# ProyectoArduino.net
KiCad netlist of a schematic drawn in EAGLE
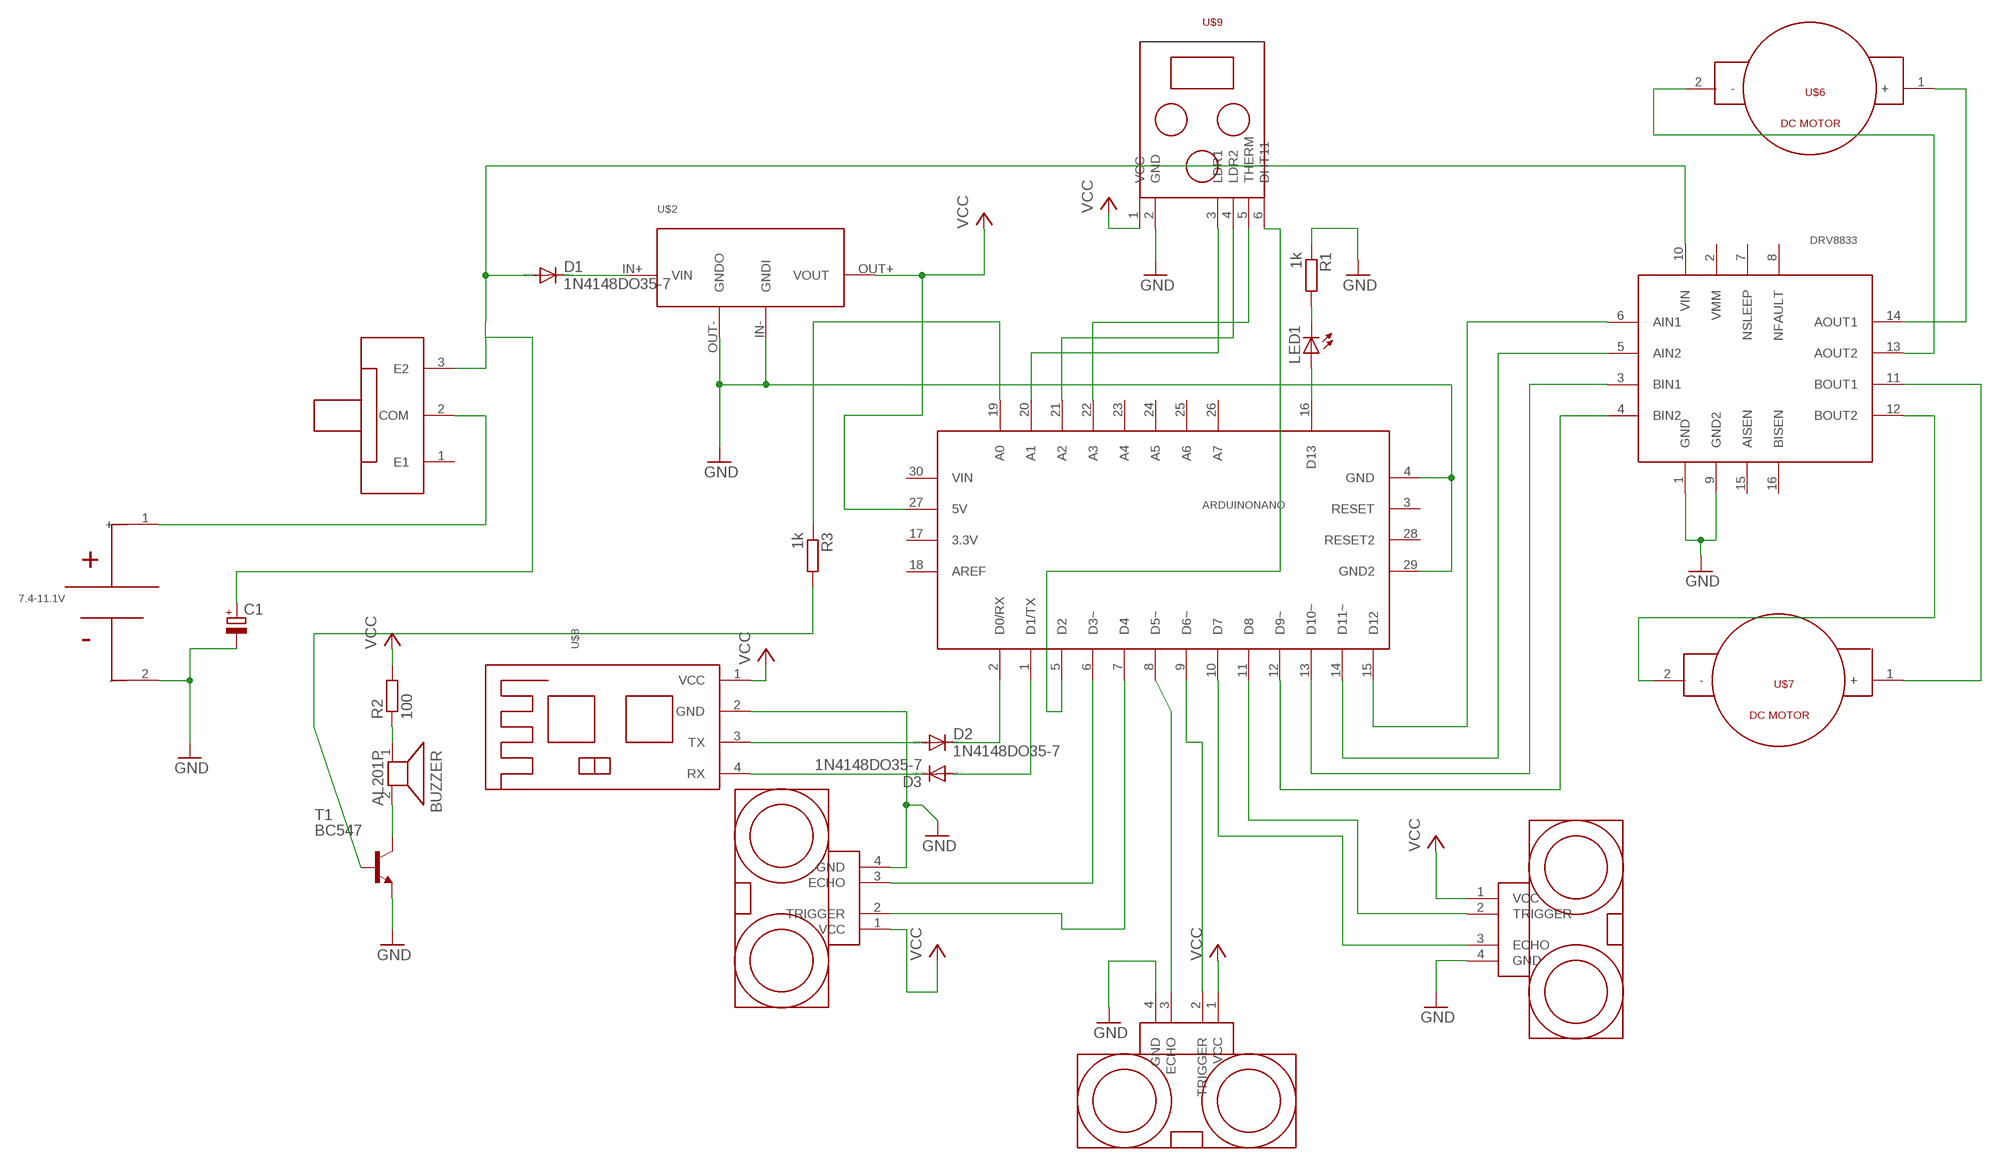
[diagram p0: schematic, sheet 1]

(export (version "E")
  (design (tool "Eeschema 10.0.6"))
  (components
    (comp (ref "7.4-11.1V")
      (value "INBAT")
      (footprint "eagle-import:INBAT")
      (libsource (lib "eagle-import") (part "INBAT"))
    )
    (comp (ref "ARDUINONANO")
      (value "NANO")
      (footprint "eagle-import:NANO")
      (libsource (lib "eagle-import") (part "NANO"))
    )
    (comp (ref "BUZZER")
      (value "AL201P")
      (footprint "eagle-import:AL201P")
      (libsource (lib "eagle-import") (part "AL201P"))
    )
    (comp (ref "C1")
      (value "CPOL-EUE3.5-10")
      (footprint "eagle-import:E3,5-10")
      (libsource (lib "eagle-import") (part "CPOL-EUE3.5-10"))
    )
    (comp (ref "D1")
      (value "1N4148DO35-7")
      (footprint "eagle-import:DO35-7")
      (libsource (lib "eagle-import") (part "1N4148DO35-7"))
    )
    (comp (ref "D2")
      (value "1N4148DO35-7")
      (footprint "eagle-import:DO35-7")
      (libsource (lib "eagle-import") (part "1N4148DO35-7"))
    )
    (comp (ref "D3")
      (value "1N4148DO35-7")
      (footprint "eagle-import:DO35-7")
      (libsource (lib "eagle-import") (part "1N4148DO35-7"))
    )
    (comp (ref "DRV8833")
      (value "MODULO")
      (footprint "eagle-import:MODULO")
      (libsource (lib "eagle-import") (part "MODULO"))
    )
    (comp (ref "LED1")
      (value "LED3MM")
      (footprint "eagle-import:LED3MM")
      (libsource (lib "eagle-import") (part "LED3MM"))
    )
    (comp (ref "R1")
      (value "1k")
      (footprint "eagle-import:0204_7")
      (libsource (lib "eagle-import") (part "R-EU_0204/7"))
    )
    (comp (ref "R2")
      (value "100")
      (footprint "eagle-import:0204_7")
      (libsource (lib "eagle-import") (part "R-EU_0204/7"))
    )
    (comp (ref "R3")
      (value "1k")
      (footprint "eagle-import:0204_7")
      (libsource (lib "eagle-import") (part "R-EU_0204/7"))
    )
    (comp (ref "T1")
      (value "BC547")
      (footprint "eagle-import:TO92")
      (libsource (lib "eagle-import") (part "BC547"))
    )
    (comp (ref "U$1")
      (value "TRIPLEPOLO")
      (footprint "eagle-import:TRIPLEPOLO")
      (libsource (lib "eagle-import") (part "TRIPLEPOLO"))
    )
    (comp (ref "U$2")
      (value "STEPDOWN")
      (footprint "eagle-import:STEPDOWN")
      (libsource (lib "eagle-import") (part "STEPDOWN"))
    )
    (comp (ref "U$3")
      (value "HC-SR04")
      (footprint "eagle-import:HC-SR04")
      (libsource (lib "eagle-import") (part "HC-SR04"))
    )
    (comp (ref "U$4")
      (value "HC-SR04")
      (footprint "eagle-import:HC-SR04")
      (libsource (lib "eagle-import") (part "HC-SR04"))
    )
    (comp (ref "U$5")
      (value "HC-SR04")
      (footprint "eagle-import:HC-SR04")
      (libsource (lib "eagle-import") (part "HC-SR04"))
    )
    (comp (ref "U$6")
      (value "OUTPUTMALE")
      (footprint "eagle-import:OUPUTMALE")
      (libsource (lib "eagle-import") (part "OUTPUTMALE"))
    )
    (comp (ref "U$7")
      (value "OUTPUTMALE")
      (footprint "eagle-import:OUPUTMALE")
      (libsource (lib "eagle-import") (part "OUTPUTMALE"))
    )
    (comp (ref "U$8")
      (value "HC-06")
      (footprint "eagle-import:HC-06")
      (libsource (lib "eagle-import") (part "HC-06"))
    )
    (comp (ref "U$9") (value "PA") (footprint "eagle-import:PA") (libsource (lib "eagle-import") (part "PA")))
  )
  (nets
    (net (code "1") (name "GND") (class "Default")
      (node (ref "7.4-11.1V") (pin "2") (pinfunction "-_2") (pintype "bidirectional"))
      (node (ref "ARDUINONANO") (pin "29") (pinfunction "GND2_29") (pintype "bidirectional"))
      (node (ref "ARDUINONANO") (pin "4") (pinfunction "GND_4") (pintype "bidirectional"))
      (node (ref "C1") (pin "-") (pinfunction "-_-") (pintype "passive"))
      (node (ref "DRV8833") (pin "1") (pinfunction "GND_1") (pintype "input"))
      (node (ref "DRV8833") (pin "9") (pinfunction "GND2_9") (pintype "input"))
      (node (ref "R1") (pin "1") (pinfunction "1_1") (pintype "passive"))
      (node (ref "T1") (pin "1") (pinfunction "E_1") (pintype "passive"))
      (node (ref "U$2") (pin "IN-") (pinfunction "GNDI_IN-") (pintype "bidirectional"))
      (node (ref "U$2") (pin "OUT-") (pinfunction "GNDO_OUT-") (pintype "bidirectional"))
      (node (ref "U$3") (pin "4") (pinfunction "GND_4") (pintype "bidirectional"))
      (node (ref "U$4") (pin "4") (pinfunction "GND_4") (pintype "bidirectional"))
      (node (ref "U$5") (pin "4") (pinfunction "GND_4") (pintype "bidirectional"))
      (node (ref "U$8") (pin "2") (pinfunction "GND_2") (pintype "bidirectional"))
      (node (ref "U$9") (pin "2") (pinfunction "GND_2") (pintype "bidirectional"))
    )
    (net (code "2") (name "Net-(7.4-11.1V-+)") (class "Default")
      (node (ref "7.4-11.1V") (pin "1") (pinfunction "+_1") (pintype "bidirectional"))
      (node (ref "U$1") (pin "2") (pinfunction "COM_2") (pintype "bidirectional"))
    )
    (net (code "3") (name "Net-(ARDUINONANO-A0)") (class "Default")
      (node (ref "ARDUINONANO") (pin "19") (pinfunction "A0_19") (pintype "bidirectional"))
      (node (ref "R3") (pin "1") (pinfunction "1_1") (pintype "passive"))
    )
    (net (code "4") (name "Net-(ARDUINONANO-A1)") (class "Default")
      (node (ref "ARDUINONANO") (pin "20") (pinfunction "A1_20") (pintype "bidirectional"))
      (node (ref "U$9") (pin "3") (pinfunction "LDR1_3") (pintype "bidirectional"))
    )
    (net (code "5") (name "Net-(ARDUINONANO-A2)") (class "Default")
      (node (ref "ARDUINONANO") (pin "21") (pinfunction "A2_21") (pintype "bidirectional"))
      (node (ref "U$9") (pin "4") (pinfunction "LDR2_4") (pintype "bidirectional"))
    )
    (net (code "6") (name "Net-(ARDUINONANO-A3)") (class "Default")
      (node (ref "ARDUINONANO") (pin "22") (pinfunction "A3_22") (pintype "bidirectional"))
      (node (ref "U$9") (pin "5") (pinfunction "THERM_5") (pintype "bidirectional"))
    )
    (net (code "7") (name "Net-(ARDUINONANO-D0{slash}RX)") (class "Default")
      (node (ref "ARDUINONANO") (pin "2") (pinfunction "D0/RX_2") (pintype "bidirectional"))
      (node (ref "D2") (pin "C") (pinfunction "C_C") (pintype "passive"))
    )
    (net (code "8") (name "Net-(ARDUINONANO-D1{slash}TX)") (class "Default")
      (node (ref "ARDUINONANO") (pin "1") (pinfunction "D1/TX_1") (pintype "bidirectional"))
      (node (ref "D3") (pin "A") (pinfunction "A_A") (pintype "passive"))
    )
    (net (code "9") (name "Net-(ARDUINONANO-D2)") (class "Default")
      (node (ref "ARDUINONANO") (pin "5") (pinfunction "D2_5") (pintype "bidirectional"))
      (node (ref "U$9") (pin "6") (pinfunction "DHT11_6") (pintype "bidirectional"))
    )
    (net (code "10") (name "Net-(ARDUINONANO-D3~{})") (class "Default")
      (node (ref "ARDUINONANO") (pin "6") (pinfunction "D3~{}_6") (pintype "bidirectional"))
      (node (ref "U$3") (pin "3") (pinfunction "ECHO_3") (pintype "bidirectional"))
    )
    (net (code "11") (name "Net-(ARDUINONANO-D4)") (class "Default")
      (node (ref "ARDUINONANO") (pin "7") (pinfunction "D4_7") (pintype "bidirectional"))
      (node (ref "U$3") (pin "2") (pinfunction "TRIGGER_2") (pintype "bidirectional"))
    )
    (net (code "12") (name "Net-(ARDUINONANO-D5~{})") (class "Default")
      (node (ref "ARDUINONANO") (pin "8") (pinfunction "D5~{}_8") (pintype "bidirectional"))
      (node (ref "U$5") (pin "3") (pinfunction "ECHO_3") (pintype "bidirectional"))
    )
    (net (code "13") (name "Net-(ARDUINONANO-D6~{})") (class "Default")
      (node (ref "ARDUINONANO") (pin "9") (pinfunction "D6~{}_9") (pintype "bidirectional"))
      (node (ref "U$5") (pin "2") (pinfunction "TRIGGER_2") (pintype "bidirectional"))
    )
    (net (code "14") (name "Net-(ARDUINONANO-D7)") (class "Default")
      (node (ref "ARDUINONANO") (pin "10") (pinfunction "D7_10") (pintype "bidirectional"))
      (node (ref "U$4") (pin "3") (pinfunction "ECHO_3") (pintype "bidirectional"))
    )
    (net (code "15") (name "Net-(ARDUINONANO-D8)") (class "Default")
      (node (ref "ARDUINONANO") (pin "11") (pinfunction "D8_11") (pintype "bidirectional"))
      (node (ref "U$4") (pin "2") (pinfunction "TRIGGER_2") (pintype "bidirectional"))
    )
    (net (code "16") (name "Net-(ARDUINONANO-D9~{})") (class "Default")
      (node (ref "ARDUINONANO") (pin "12") (pinfunction "D9~{}_12") (pintype "bidirectional"))
      (node (ref "DRV8833") (pin "4") (pinfunction "BIN2_4") (pintype "input"))
    )
    (net (code "17") (name "Net-(ARDUINONANO-D10~{})") (class "Default")
      (node (ref "ARDUINONANO") (pin "13") (pinfunction "D10~{}_13") (pintype "bidirectional"))
      (node (ref "DRV8833") (pin "3") (pinfunction "BIN1_3") (pintype "input"))
    )
    (net (code "18") (name "Net-(ARDUINONANO-D11~{})") (class "Default")
      (node (ref "ARDUINONANO") (pin "14") (pinfunction "D11~{}_14") (pintype "bidirectional"))
      (node (ref "DRV8833") (pin "5") (pinfunction "AIN2_5") (pintype "input"))
    )
    (net (code "19") (name "Net-(ARDUINONANO-D12)") (class "Default")
      (node (ref "ARDUINONANO") (pin "15") (pinfunction "D12_15") (pintype "bidirectional"))
      (node (ref "DRV8833") (pin "6") (pinfunction "AIN1_6") (pintype "input"))
    )
    (net (code "20") (name "Net-(ARDUINONANO-D13)") (class "Default")
      (node (ref "ARDUINONANO") (pin "16") (pinfunction "D13_16") (pintype "bidirectional"))
      (node (ref "LED1") (pin "A") (pinfunction "A_A") (pintype "passive"))
    )
    (net (code "21") (name "Net-(BUZZER-Pad1)") (class "Default")
      (node (ref "BUZZER") (pin "1") (pinfunction "1_1") (pintype "passive"))
      (node (ref "R2") (pin "1") (pinfunction "1_1") (pintype "passive"))
    )
    (net (code "22") (name "Net-(DRV8833-AOUT1)") (class "Default")
      (node (ref "DRV8833") (pin "14") (pinfunction "AOUT1_14") (pintype "output"))
      (node (ref "U$6") (pin "1") (pinfunction "+_1") (pintype "bidirectional"))
    )
    (net (code "23") (name "Net-(DRV8833-AOUT2)") (class "Default")
      (node (ref "DRV8833") (pin "13") (pinfunction "AOUT2_13") (pintype "output"))
      (node (ref "U$6") (pin "2") (pinfunction "-_2") (pintype "bidirectional"))
    )
    (net (code "24") (name "Net-(DRV8833-BOUT1)") (class "Default")
      (node (ref "DRV8833") (pin "11") (pinfunction "BOUT1_11") (pintype "output"))
      (node (ref "U$7") (pin "1") (pinfunction "+_1") (pintype "bidirectional"))
    )
    (net (code "25") (name "Net-(DRV8833-BOUT2)") (class "Default")
      (node (ref "DRV8833") (pin "12") (pinfunction "BOUT2_12") (pintype "output"))
      (node (ref "U$7") (pin "2") (pinfunction "-_2") (pintype "bidirectional"))
    )
    (net (code "26") (name "Net-(DRV8833-VIN)") (class "Default")
      (node (ref "C1") (pin "+") (pinfunction "+_+") (pintype "passive"))
      (node (ref "D1") (pin "A") (pinfunction "A_A") (pintype "passive"))
      (node (ref "DRV8833") (pin "10") (pinfunction "VIN_10") (pintype "input"))
      (node (ref "U$1") (pin "3") (pinfunction "E2_3") (pintype "bidirectional"))
    )
    (net (code "27") (name "Net-(LED1-C)") (class "Default")
      (node (ref "LED1") (pin "K") (pinfunction "C_K") (pintype "passive"))
      (node (ref "R1") (pin "2") (pinfunction "2_2") (pintype "passive"))
    )
    (net (code "28") (name "Net-(T1-B)") (class "Default")
      (node (ref "R3") (pin "2") (pinfunction "2_2") (pintype "passive"))
      (node (ref "T1") (pin "2") (pinfunction "B_2") (pintype "passive"))
    )
    (net (code "29") (name "Net-(T1-C)") (class "Default")
      (node (ref "BUZZER") (pin "2") (pinfunction "2_2") (pintype "passive"))
      (node (ref "T1") (pin "3") (pinfunction "C_3") (pintype "passive"))
    )
    (net (code "30") (name "Net-(U$2-VIN)") (class "Default")
      (node (ref "D1") (pin "C") (pinfunction "C_C") (pintype "passive"))
      (node (ref "U$2") (pin "IN+") (pinfunction "VIN_IN+") (pintype "bidirectional"))
    )
    (net (code "31") (name "Net-(U$8-RX)") (class "Default")
      (node (ref "D3") (pin "C") (pinfunction "C_C") (pintype "passive"))
      (node (ref "U$8") (pin "4") (pinfunction "RX_4") (pintype "bidirectional"))
    )
    (net (code "32") (name "Net-(U$8-TX)") (class "Default")
      (node (ref "D2") (pin "A") (pinfunction "A_A") (pintype "passive"))
      (node (ref "U$8") (pin "3") (pinfunction "TX_3") (pintype "bidirectional"))
    )
    (net (code "33") (name "VCC") (class "Default")
      (node (ref "ARDUINONANO") (pin "27") (pinfunction "5V_27") (pintype "bidirectional"))
      (node (ref "R2") (pin "2") (pinfunction "2_2") (pintype "passive"))
      (node (ref "U$2") (pin "OUT+") (pinfunction "VOUT_OUT+") (pintype "bidirectional"))
      (node (ref "U$3") (pin "1") (pinfunction "VCC_1") (pintype "bidirectional"))
      (node (ref "U$4") (pin "1") (pinfunction "VCC_1") (pintype "bidirectional"))
      (node (ref "U$5") (pin "1") (pinfunction "VCC_1") (pintype "bidirectional"))
      (node (ref "U$8") (pin "1") (pinfunction "VCC_1") (pintype "bidirectional"))
      (node (ref "U$9") (pin "1") (pinfunction "VCC_1") (pintype "bidirectional"))
    )
    (net (code "34") (name "unconnected-(ARDUINONANO-3.3V-Pad17)") (class "Default")
      (node (ref "ARDUINONANO") (pin "17") (pinfunction "3.3V_17") (pintype "bidirectional"))
    )
    (net (code "35") (name "unconnected-(ARDUINONANO-A4-Pad23)") (class "Default")
      (node (ref "ARDUINONANO") (pin "23") (pinfunction "A4_23") (pintype "bidirectional"))
    )
    (net (code "36") (name "unconnected-(ARDUINONANO-A5-Pad24)") (class "Default")
      (node (ref "ARDUINONANO") (pin "24") (pinfunction "A5_24") (pintype "bidirectional"))
    )
    (net (code "37") (name "unconnected-(ARDUINONANO-A6-Pad25)") (class "Default")
      (node (ref "ARDUINONANO") (pin "25") (pinfunction "A6_25") (pintype "bidirectional"))
    )
    (net (code "38") (name "unconnected-(ARDUINONANO-A7-Pad26)") (class "Default")
      (node (ref "ARDUINONANO") (pin "26") (pinfunction "A7_26") (pintype "bidirectional"))
    )
    (net (code "39") (name "unconnected-(ARDUINONANO-AREF-Pad18)") (class "Default")
      (node (ref "ARDUINONANO") (pin "18") (pinfunction "AREF_18") (pintype "bidirectional"))
    )
    (net (code "40") (name "unconnected-(ARDUINONANO-RESET-Pad3)") (class "Default")
      (node (ref "ARDUINONANO") (pin "3") (pinfunction "RESET_3") (pintype "bidirectional"))
    )
    (net (code "41") (name "unconnected-(ARDUINONANO-RESET2-Pad28)") (class "Default")
      (node (ref "ARDUINONANO") (pin "28") (pinfunction "RESET2_28") (pintype "bidirectional"))
    )
    (net (code "42") (name "unconnected-(ARDUINONANO-VIN-Pad30)") (class "Default")
      (node (ref "ARDUINONANO") (pin "30") (pinfunction "VIN_30") (pintype "bidirectional"))
    )
    (net (code "43") (name "unconnected-(DRV8833-AISEN-Pad15)") (class "Default")
      (node (ref "DRV8833") (pin "15") (pinfunction "AISEN_15") (pintype "input"))
    )
    (net (code "44") (name "unconnected-(DRV8833-BISEN-Pad16)") (class "Default")
      (node (ref "DRV8833") (pin "16") (pinfunction "BISEN_16") (pintype "input"))
    )
    (net (code "45") (name "unconnected-(DRV8833-NFAULT-Pad8)") (class "Default")
      (node (ref "DRV8833") (pin "8") (pinfunction "NFAULT_8") (pintype "input"))
    )
    (net (code "46") (name "unconnected-(DRV8833-NSLEEP-Pad7)") (class "Default")
      (node (ref "DRV8833") (pin "7") (pinfunction "NSLEEP_7") (pintype "input"))
    )
    (net (code "47") (name "unconnected-(DRV8833-VMM-Pad2)") (class "Default")
      (node (ref "DRV8833") (pin "2") (pinfunction "VMM_2") (pintype "input"))
    )
    (net (code "48") (name "unconnected-(U$1-E1-Pad1)") (class "Default")
      (node (ref "U$1") (pin "1") (pinfunction "E1_1") (pintype "bidirectional"))
    )
  )
)
